# Sampler.net
KiCad netlist of a schematic drawn in Altium Designer
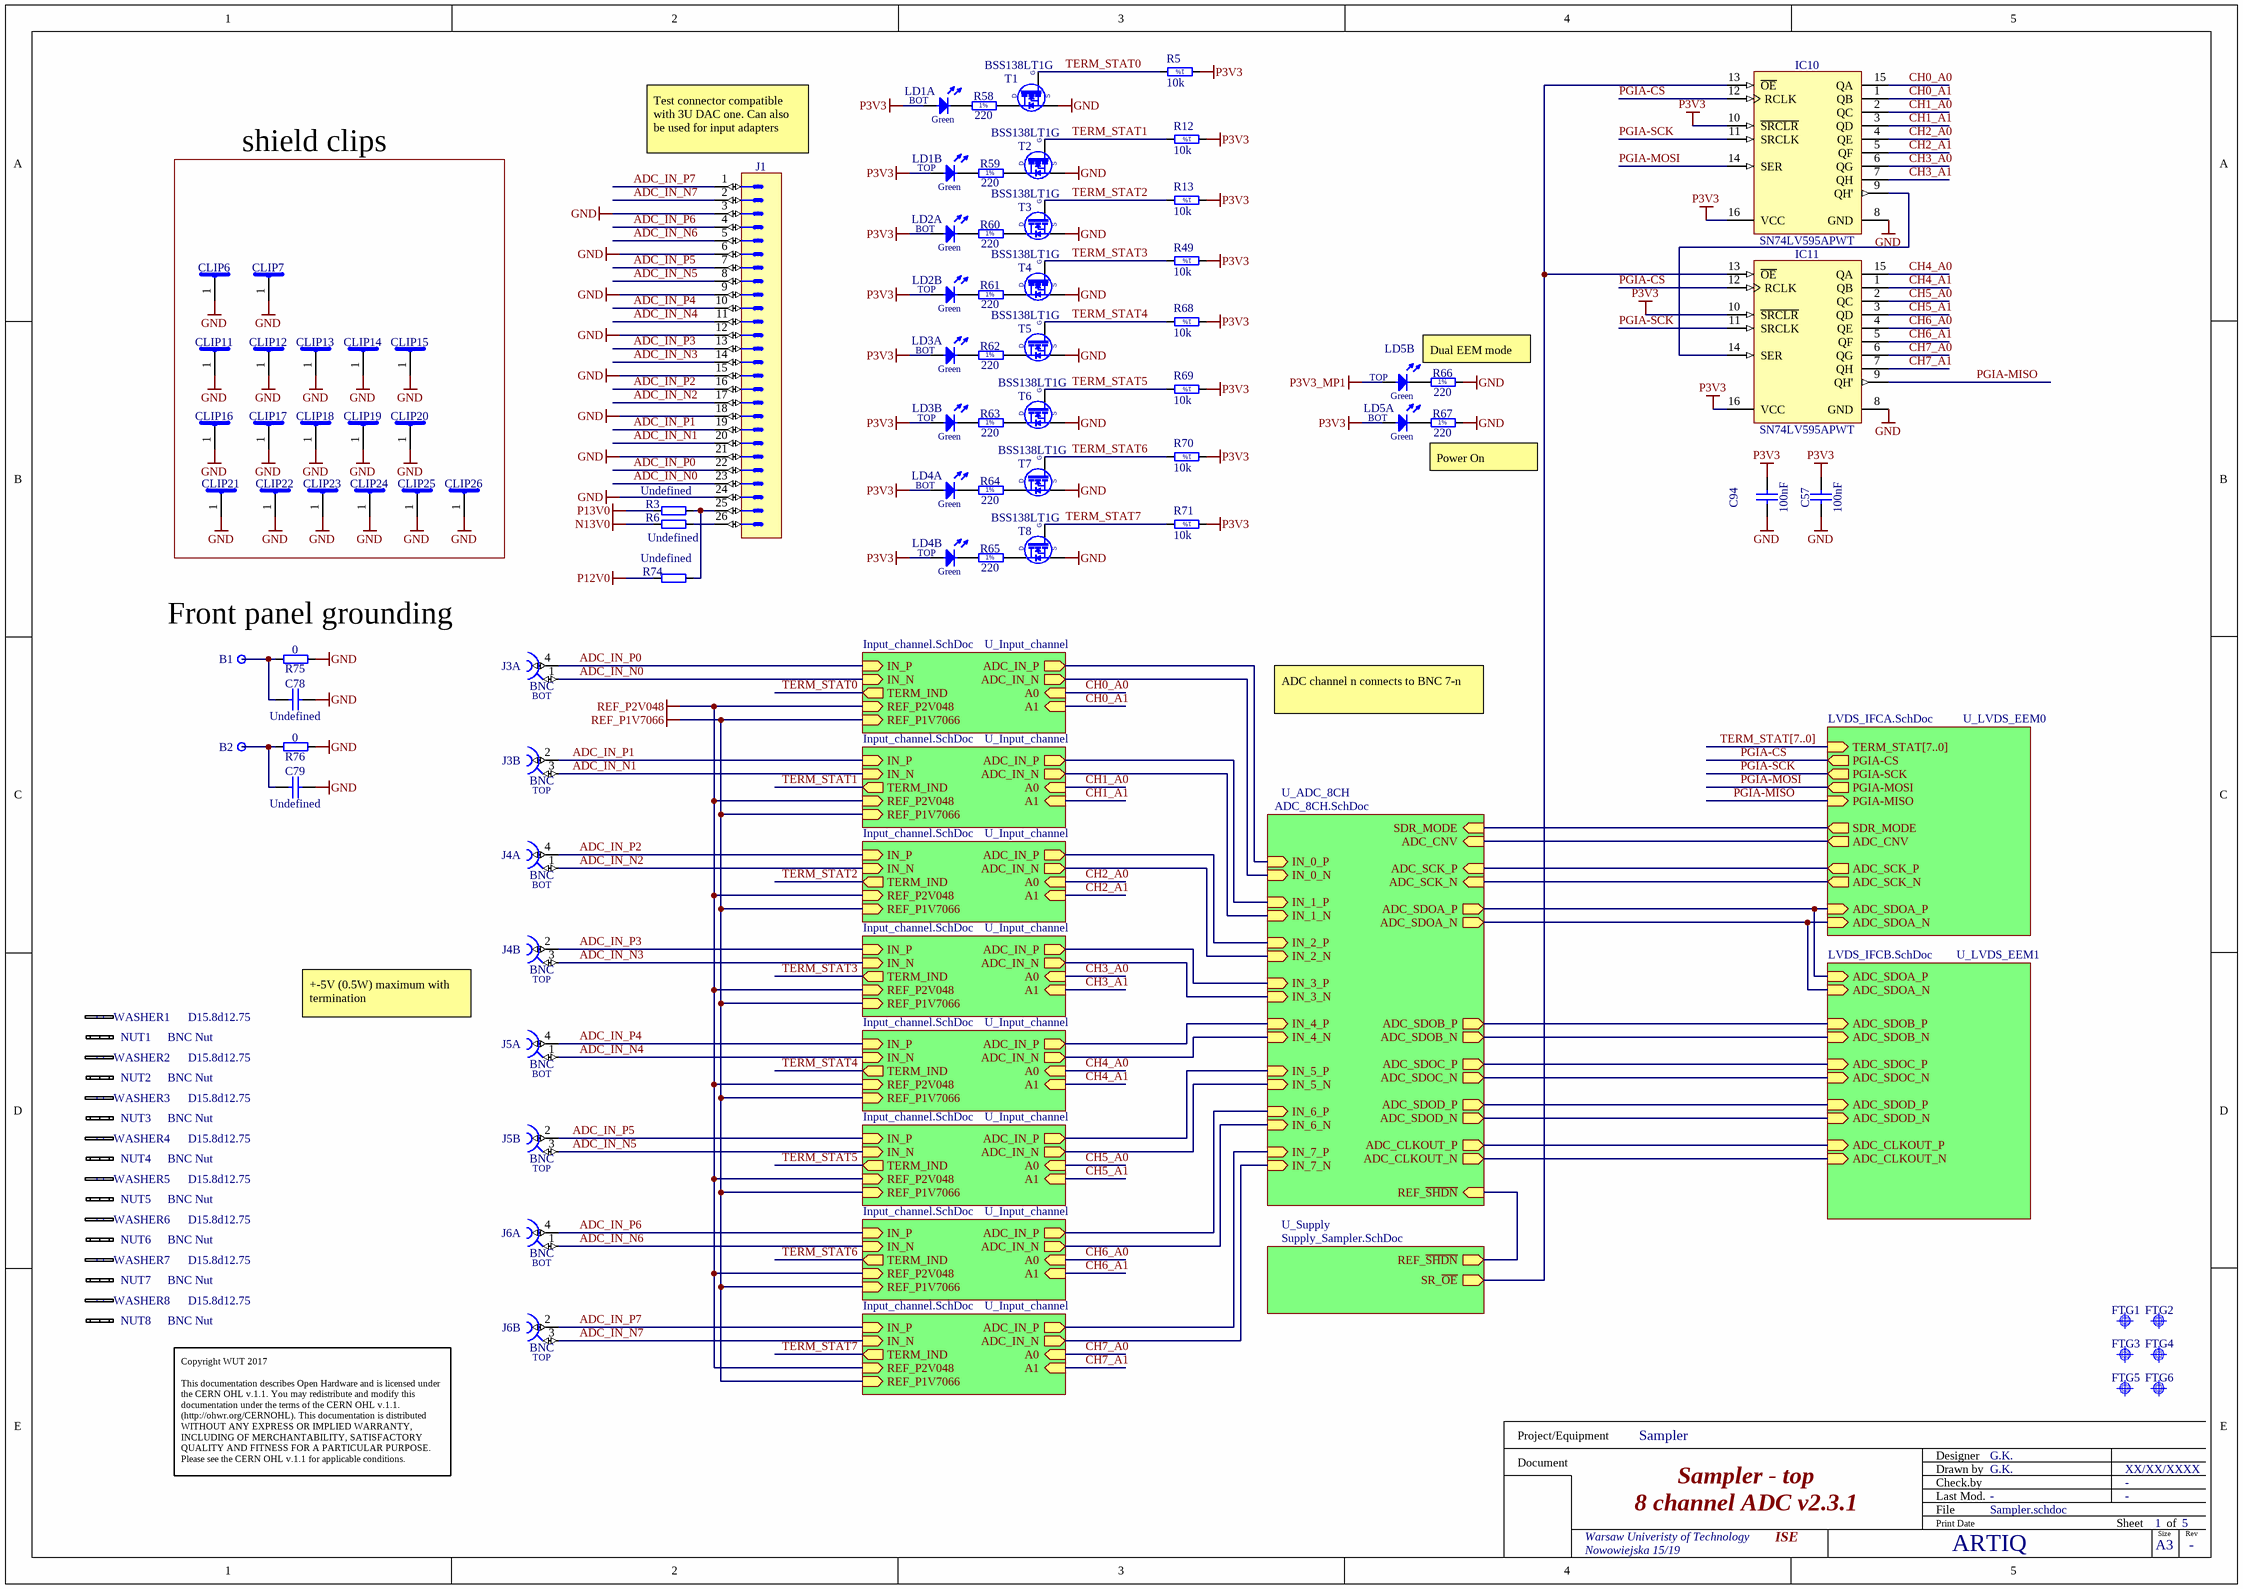
[diagram p0: Sampler.schdoc]

(export (version "E")
  (design (tool "Eeschema 10.0.6"))
  (components
    (comp (ref "B1")
      (value "Plated Hole")
      (footprint "MTG270_500")
      (description "Single Terminal Socket")
      (fields (field (name "PART NUMBER") "PLATED_HOLE2.7_PAD5.0") (field (name "AUTHOR") "CERN DEM JMW"))
      (libsource (lib "Eletro-mechanical") (part "Single Terminal Socket"))
    )
    (comp (ref "B2")
      (value "Plated Hole")
      (footprint "MTG270_500")
      (description "Single Terminal Socket")
      (fields (field (name "PART NUMBER") "PLATED_HOLE2.7_PAD5.0") (field (name "AUTHOR") "CERN DEM JMW"))
      (libsource (lib "Eletro-mechanical") (part "Single Terminal Socket"))
    )
    (comp (ref "C57")
      (value "100nF")
      (footprint "CAPC1608X87N")
      (description "Non-polarised capacitor")
      (fields
        (field (name "PART NUMBER") "CC0603_100NF_50V_10%_X7R")
        (field (name "VOLTAGE") "50V")
        (field (name "AUTHOR") "CERN DEM JLC")
      )
      (libsource (lib "Capacitors") (part "Capacitor - non polarized"))
    )
    (comp (ref "C78")
      (value "Undefined")
      (footprint "CAPC2012X135N")
      (description "Non-polarised capacitor")
      (fields (field (name "PART NUMBER") "CC0805_NO-VALUE") (field (name "AUTHOR") "CERN DEM JLC"))
      (libsource (lib "Capacitors") (part "Capacitor - non polarized"))
    )
    (comp (ref "C79")
      (value "Undefined")
      (footprint "CAPC2012X135N")
      (description "Non-polarised capacitor")
      (fields (field (name "PART NUMBER") "CC0805_NO-VALUE") (field (name "AUTHOR") "CERN DEM JLC"))
      (libsource (lib "Capacitors") (part "Capacitor - non polarized"))
    )
    (comp (ref "C94")
      (value "100nF")
      (footprint "CAPC1608X87N")
      (description "Non-polarised capacitor")
      (fields
        (field (name "PART NUMBER") "CC0603_100NF_50V_10%_X7R")
        (field (name "VOLTAGE") "50V")
        (field (name "AUTHOR") "CERN DEM JLC")
      )
      (libsource (lib "Capacitors") (part "Capacitor - non polarized"))
    )
    (comp (ref "CLIP6")
      (value "S1411-46R")
      (footprint "CLIP_HOLLAND-SHIELDING_LC")
      (description "Surface Mount Clip for PCB Screening Covers")
      (fields (field (name "MANUFACTURER") "HARWIN") (field (name "AUTHOR") "CERN DEM JLC"))
      (libsource (lib "LIBRARY_SCH") (part "SHIELD_CLIP"))
    )
    (comp (ref "CLIP7")
      (value "S1411-46R")
      (footprint "CLIP_HOLLAND-SHIELDING_LC")
      (description "Surface Mount Clip for PCB Screening Covers")
      (fields (field (name "MANUFACTURER") "HARWIN") (field (name "AUTHOR") "CERN DEM JLC"))
      (libsource (lib "LIBRARY_SCH") (part "SHIELD_CLIP"))
    )
    (comp (ref "CLIP11")
      (value "S1411-46R")
      (footprint "CLIP_HOLLAND-SHIELDING_LC")
      (description "Surface Mount Clip for PCB Screening Covers")
      (fields (field (name "MANUFACTURER") "HARWIN") (field (name "AUTHOR") "CERN DEM JLC"))
      (libsource (lib "LIBRARY_SCH") (part "SHIELD_CLIP"))
    )
    (comp (ref "CLIP12")
      (value "S1411-46R")
      (footprint "CLIP_HOLLAND-SHIELDING_LC")
      (description "Surface Mount Clip for PCB Screening Covers")
      (fields (field (name "MANUFACTURER") "HARWIN") (field (name "AUTHOR") "CERN DEM JLC"))
      (libsource (lib "LIBRARY_SCH") (part "SHIELD_CLIP"))
    )
    (comp (ref "CLIP13")
      (value "S1411-46R")
      (footprint "CLIP_HOLLAND-SHIELDING_LC")
      (description "Surface Mount Clip for PCB Screening Covers")
      (fields (field (name "MANUFACTURER") "HARWIN") (field (name "AUTHOR") "CERN DEM JLC"))
      (libsource (lib "LIBRARY_SCH") (part "SHIELD_CLIP"))
    )
    (comp (ref "CLIP14")
      (value "S1411-46R")
      (footprint "CLIP_HOLLAND-SHIELDING_LC")
      (description "Surface Mount Clip for PCB Screening Covers")
      (fields (field (name "MANUFACTURER") "HARWIN") (field (name "AUTHOR") "CERN DEM JLC"))
      (libsource (lib "LIBRARY_SCH") (part "SHIELD_CLIP"))
    )
    (comp (ref "CLIP15")
      (value "S1411-46R")
      (footprint "CLIP_HOLLAND-SHIELDING_LC")
      (description "Surface Mount Clip for PCB Screening Covers")
      (fields (field (name "MANUFACTURER") "HARWIN") (field (name "AUTHOR") "CERN DEM JLC"))
      (libsource (lib "LIBRARY_SCH") (part "SHIELD_CLIP"))
    )
    (comp (ref "CLIP16")
      (value "S1411-46R")
      (footprint "CLIP_HOLLAND-SHIELDING_LC")
      (description "Surface Mount Clip for PCB Screening Covers")
      (fields (field (name "MANUFACTURER") "HARWIN") (field (name "AUTHOR") "CERN DEM JLC"))
      (libsource (lib "LIBRARY_SCH") (part "SHIELD_CLIP"))
    )
    (comp (ref "CLIP17")
      (value "S1411-46R")
      (footprint "CLIP_HOLLAND-SHIELDING_LC")
      (description "Surface Mount Clip for PCB Screening Covers")
      (fields (field (name "MANUFACTURER") "HARWIN") (field (name "AUTHOR") "CERN DEM JLC"))
      (libsource (lib "LIBRARY_SCH") (part "SHIELD_CLIP"))
    )
    (comp (ref "CLIP18")
      (value "S1411-46R")
      (footprint "CLIP_HOLLAND-SHIELDING_LC")
      (description "Surface Mount Clip for PCB Screening Covers")
      (fields (field (name "MANUFACTURER") "HARWIN") (field (name "AUTHOR") "CERN DEM JLC"))
      (libsource (lib "LIBRARY_SCH") (part "SHIELD_CLIP"))
    )
    (comp (ref "CLIP19")
      (value "S1411-46R")
      (footprint "CLIP_HOLLAND-SHIELDING_LC")
      (description "Surface Mount Clip for PCB Screening Covers")
      (fields (field (name "MANUFACTURER") "HARWIN") (field (name "AUTHOR") "CERN DEM JLC"))
      (libsource (lib "LIBRARY_SCH") (part "SHIELD_CLIP"))
    )
    (comp (ref "CLIP20")
      (value "S1411-46R")
      (footprint "CLIP_HOLLAND-SHIELDING_LC")
      (description "Surface Mount Clip for PCB Screening Covers")
      (fields (field (name "MANUFACTURER") "HARWIN") (field (name "AUTHOR") "CERN DEM JLC"))
      (libsource (lib "LIBRARY_SCH") (part "SHIELD_CLIP"))
    )
    (comp (ref "CLIP21")
      (value "S1411-46R")
      (footprint "CLIP_HOLLAND-SHIELDING_LC")
      (description "Surface Mount Clip for PCB Screening Covers")
      (fields (field (name "MANUFACTURER") "HARWIN") (field (name "AUTHOR") "CERN DEM JLC"))
      (libsource (lib "LIBRARY_SCH") (part "SHIELD_CLIP"))
    )
    (comp (ref "CLIP22")
      (value "S1411-46R")
      (footprint "CLIP_HOLLAND-SHIELDING_LC")
      (description "Surface Mount Clip for PCB Screening Covers")
      (fields (field (name "MANUFACTURER") "HARWIN") (field (name "AUTHOR") "CERN DEM JLC"))
      (libsource (lib "LIBRARY_SCH") (part "SHIELD_CLIP"))
    )
    (comp (ref "CLIP23")
      (value "S1411-46R")
      (footprint "CLIP_HOLLAND-SHIELDING_LC")
      (description "Surface Mount Clip for PCB Screening Covers")
      (fields (field (name "MANUFACTURER") "HARWIN") (field (name "AUTHOR") "CERN DEM JLC"))
      (libsource (lib "LIBRARY_SCH") (part "SHIELD_CLIP"))
    )
    (comp (ref "CLIP24")
      (value "S1411-46R")
      (footprint "CLIP_HOLLAND-SHIELDING_LC")
      (description "Surface Mount Clip for PCB Screening Covers")
      (fields (field (name "MANUFACTURER") "HARWIN") (field (name "AUTHOR") "CERN DEM JLC"))
      (libsource (lib "LIBRARY_SCH") (part "SHIELD_CLIP"))
    )
    (comp (ref "CLIP25")
      (value "S1411-46R")
      (footprint "CLIP_HOLLAND-SHIELDING_LC")
      (description "Surface Mount Clip for PCB Screening Covers")
      (fields (field (name "MANUFACTURER") "HARWIN") (field (name "AUTHOR") "CERN DEM JLC"))
      (libsource (lib "LIBRARY_SCH") (part "SHIELD_CLIP"))
    )
    (comp (ref "CLIP26")
      (value "S1411-46R")
      (footprint "CLIP_HOLLAND-SHIELDING_LC")
      (description "Surface Mount Clip for PCB Screening Covers")
      (fields (field (name "MANUFACTURER") "HARWIN") (field (name "AUTHOR") "CERN DEM JLC"))
      (libsource (lib "LIBRARY_SCH") (part "SHIELD_CLIP"))
    )
    (comp (ref "FTG1")
      (value "Use only in PCB")
      (footprint "FIDUCIAL_TOP_C100-200")
      (description "Fiducial Target")
      (fields (field (name "PART NUMBER") "FIDUCIAL_TARGET_C100-200") (field (name "AUTHOR") "CERN DEM JLC"))
      (libsource (lib "Eletro-mechanical") (part "Fiducial Target"))
    )
    (comp (ref "FTG2")
      (value "Use only in PCB")
      (footprint "FIDUCIAL_TOP_C100-200")
      (description "Fiducial Target")
      (fields (field (name "PART NUMBER") "FIDUCIAL_TARGET_C100-200") (field (name "AUTHOR") "CERN DEM JLC"))
      (libsource (lib "Eletro-mechanical") (part "Fiducial Target"))
    )
    (comp (ref "FTG3")
      (value "Use only in PCB")
      (footprint "FIDUCIAL_TOP_S100-200")
      (description "Fiducial Target")
      (fields (field (name "PART NUMBER") "FIDUCIAL_TARGET_S100-200") (field (name "AUTHOR") "CERN DEM JLC"))
      (libsource (lib "Eletro-mechanical") (part "Fiducial Target"))
    )
    (comp (ref "FTG4")
      (value "Use only in PCB")
      (footprint "FIDUCIAL_TOP_S100-200")
      (description "Fiducial Target")
      (fields (field (name "PART NUMBER") "FIDUCIAL_TARGET_S100-200") (field (name "AUTHOR") "CERN DEM JLC"))
      (libsource (lib "Eletro-mechanical") (part "Fiducial Target"))
    )
    (comp (ref "FTG5")
      (value "Use only in PCB")
      (footprint "FIDUCIAL_TOP_S100-200")
      (description "Fiducial Target")
      (fields (field (name "PART NUMBER") "FIDUCIAL_TARGET_S100-200") (field (name "AUTHOR") "CERN DEM JLC"))
      (libsource (lib "Eletro-mechanical") (part "Fiducial Target"))
    )
    (comp (ref "FTG6")
      (value "Use only in PCB")
      (footprint "FIDUCIAL_TOP_S100-200")
      (description "Fiducial Target")
      (fields (field (name "PART NUMBER") "FIDUCIAL_TARGET_S100-200") (field (name "AUTHOR") "CERN DEM JLC"))
      (libsource (lib "Eletro-mechanical") (part "Fiducial Target"))
    )
    (comp (ref "IC10")
      (value "SN74LV595APWT")
      (footprint "SOP65P640X120-16N")
      (description "8-Bit Shift Register With 3-State Output Register")
      (fields (field (name "MANUFACTURER") "TEXAS INSTRUMENTS") (field (name "AUTHOR") "CERN DEM JLC"))
      (libsource (lib "ICs And Semiconductors") (part "74595"))
    )
    (comp (ref "IC11")
      (value "SN74LV595APWT")
      (footprint "SOP65P640X120-16N")
      (description "8-Bit Shift Register With 3-State Output Register")
      (fields (field (name "MANUFACTURER") "TEXAS INSTRUMENTS") (field (name "AUTHOR") "CERN DEM JLC"))
      (libsource (lib "ICs And Semiconductors") (part "74595"))
    )
    (comp (ref "J1")
      (value "Header 26")
      (footprint "3M_N2526-6002RB")
      (description "Connector 26 Male")
      (fields
        (field (name "PART NUMBER") "3M_N2526-6002RB")
        (field (name "MANUFACTURER") "3M")
        (field (name "AUTHOR") "CERN DEM JLC")
      )
      (libsource (lib "Connectors") (part "Connector 26 Male"))
    )
    (comp (ref "J3")
      (value "BNC")
      (footprint "RENHOTEC_RHT-610-0049")
      (description "Dual Right Angle 50 Ohm BNC Jack, White Valox Case")
      (fields
        (field (name "PART NUMBER") "RENHOTEC_RHT-610-0049")
        (field (name "MANUFACTURER") "RENHOTEC")
        (field (name "AUTHOR") "GK")
      )
      (libsource (lib "LIBRARY_SCH") (part "CON_BNC_DUAL"))
    )
    (comp (ref "J4")
      (value "BNC")
      (footprint "RENHOTEC_RHT-610-0049")
      (description "Dual Right Angle 50 Ohm BNC Jack, White Valox Case")
      (fields
        (field (name "PART NUMBER") "RENHOTEC_RHT-610-0049")
        (field (name "MANUFACTURER") "RENHOTEC")
        (field (name "AUTHOR") "GK")
      )
      (libsource (lib "LIBRARY_SCH") (part "CON_BNC_DUAL"))
    )
    (comp (ref "J5")
      (value "BNC")
      (footprint "RENHOTEC_RHT-610-0049")
      (description "Dual Right Angle 50 Ohm BNC Jack, White Valox Case")
      (fields
        (field (name "PART NUMBER") "RENHOTEC_RHT-610-0049")
        (field (name "MANUFACTURER") "RENHOTEC")
        (field (name "AUTHOR") "GK")
      )
      (libsource (lib "LIBRARY_SCH") (part "CON_BNC_DUAL"))
    )
    (comp (ref "J6")
      (value "BNC")
      (footprint "RENHOTEC_RHT-610-0049")
      (description "Dual Right Angle 50 Ohm BNC Jack, White Valox Case")
      (fields
        (field (name "PART NUMBER") "RENHOTEC_RHT-610-0049")
        (field (name "MANUFACTURER") "RENHOTEC")
        (field (name "AUTHOR") "GK")
      )
      (libsource (lib "LIBRARY_SCH") (part "CON_BNC_DUAL"))
    )
    (comp (ref "LD1")
      (value "Green/Green")
      (footprint "LED_DIALIGHT_571-0122F")
      (description "LED x2 Green 1C2A-BOT_3C4A-TOP")
      (fields
        (field (name "PART NUMBER") "LED_DIALIGHT_571-0122F")
        (field (name "MANUFACTURER") "DIALIGHT")
        (field (name "AUTHOR") "CERN DEM JLC")
      )
      (libsource (lib "ICs And Semiconductors") (part "LED x2 Green 1C2A-BOT_3C4A-TOP"))
    )
    (comp (ref "LD2")
      (value "Green/Green")
      (footprint "LED_DIALIGHT_571-0122F")
      (description "LED x2 Green 1C2A-BOT_3C4A-TOP")
      (fields
        (field (name "PART NUMBER") "LED_DIALIGHT_571-0122F")
        (field (name "MANUFACTURER") "DIALIGHT")
        (field (name "AUTHOR") "CERN DEM JLC")
      )
      (libsource (lib "ICs And Semiconductors") (part "LED x2 Green 1C2A-BOT_3C4A-TOP"))
    )
    (comp (ref "LD3")
      (value "Green/Green")
      (footprint "LED_DIALIGHT_571-0122F")
      (description "LED x2 Green 1C2A-BOT_3C4A-TOP")
      (fields
        (field (name "PART NUMBER") "LED_DIALIGHT_571-0122F")
        (field (name "MANUFACTURER") "DIALIGHT")
        (field (name "AUTHOR") "CERN DEM JLC")
      )
      (libsource (lib "ICs And Semiconductors") (part "LED x2 Green 1C2A-BOT_3C4A-TOP"))
    )
    (comp (ref "LD4")
      (value "Green/Green")
      (footprint "LED_DIALIGHT_571-0122F")
      (description "LED x2 Green 1C2A-BOT_3C4A-TOP")
      (fields
        (field (name "PART NUMBER") "LED_DIALIGHT_571-0122F")
        (field (name "MANUFACTURER") "DIALIGHT")
        (field (name "AUTHOR") "CERN DEM JLC")
      )
      (libsource (lib "ICs And Semiconductors") (part "LED x2 Green 1C2A-BOT_3C4A-TOP"))
    )
    (comp (ref "LD5")
      (value "Green/Green")
      (footprint "LED_DIALIGHT_571-0122F")
      (description "LED x2 Green 1C2A-BOT_3C4A-TOP")
      (fields
        (field (name "PART NUMBER") "LED_DIALIGHT_571-0122F")
        (field (name "MANUFACTURER") "DIALIGHT")
        (field (name "AUTHOR") "CERN DEM JLC")
      )
      (libsource (lib "ICs And Semiconductors") (part "LED x2 Green 1C2A-BOT_3C4A-TOP"))
    )
    (comp (ref "NUT1")
      (value "BNC Nut")
      (footprint "TE_1-329631-2")
      (description "BNC nut")
      (fields
        (field (name "PART NUMBER") "TE_1-329631-2")
        (field (name "MANUFACTURER") "TE")
        (field (name "AUTHOR") "CERN DEM JLC")
      )
      (libsource (lib "Mechanical") (part "MECH_BNC_NUT"))
    )
    (comp (ref "NUT2")
      (value "BNC Nut")
      (footprint "TE_1-329631-2")
      (description "BNC nut")
      (fields
        (field (name "PART NUMBER") "TE_1-329631-2")
        (field (name "MANUFACTURER") "TE")
        (field (name "AUTHOR") "CERN DEM JLC")
      )
      (libsource (lib "Mechanical") (part "MECH_BNC_NUT"))
    )
    (comp (ref "NUT3")
      (value "BNC Nut")
      (footprint "TE_1-329631-2")
      (description "BNC nut")
      (fields
        (field (name "PART NUMBER") "TE_1-329631-2")
        (field (name "MANUFACTURER") "TE")
        (field (name "AUTHOR") "CERN DEM JLC")
      )
      (libsource (lib "Mechanical") (part "MECH_BNC_NUT"))
    )
    (comp (ref "NUT4")
      (value "BNC Nut")
      (footprint "TE_1-329631-2")
      (description "BNC nut")
      (fields
        (field (name "PART NUMBER") "TE_1-329631-2")
        (field (name "MANUFACTURER") "TE")
        (field (name "AUTHOR") "CERN DEM JLC")
      )
      (libsource (lib "Mechanical") (part "MECH_BNC_NUT"))
    )
    (comp (ref "NUT5")
      (value "BNC Nut")
      (footprint "TE_1-329631-2")
      (description "BNC nut")
      (fields
        (field (name "PART NUMBER") "TE_1-329631-2")
        (field (name "MANUFACTURER") "TE")
        (field (name "AUTHOR") "CERN DEM JLC")
      )
      (libsource (lib "Mechanical") (part "MECH_BNC_NUT"))
    )
    (comp (ref "NUT6")
      (value "BNC Nut")
      (footprint "TE_1-329631-2")
      (description "BNC nut")
      (fields
        (field (name "PART NUMBER") "TE_1-329631-2")
        (field (name "MANUFACTURER") "TE")
        (field (name "AUTHOR") "CERN DEM JLC")
      )
      (libsource (lib "Mechanical") (part "MECH_BNC_NUT"))
    )
    (comp (ref "NUT7")
      (value "BNC Nut")
      (footprint "TE_1-329631-2")
      (description "BNC nut")
      (fields
        (field (name "PART NUMBER") "TE_1-329631-2")
        (field (name "MANUFACTURER") "TE")
        (field (name "AUTHOR") "CERN DEM JLC")
      )
      (libsource (lib "Mechanical") (part "MECH_BNC_NUT"))
    )
    (comp (ref "NUT8")
      (value "BNC Nut")
      (footprint "TE_1-329631-2")
      (description "BNC nut")
      (fields
        (field (name "PART NUMBER") "TE_1-329631-2")
        (field (name "MANUFACTURER") "TE")
        (field (name "AUTHOR") "CERN DEM JLC")
      )
      (libsource (lib "Mechanical") (part "MECH_BNC_NUT"))
    )
    (comp (ref "R3")
      (value "Undefined")
      (footprint "RESC1608X55N")
      (description "Resistor")
      (fields (field (name "PART NUMBER") "R0603_NO-VALUE") (field (name "AUTHOR") "CERN DEM JLC"))
      (libsource (lib "Resistors") (part "Resistor"))
    )
    (comp (ref "R5")
      (value "10k")
      (footprint "RESC1005X40N")
      (description "Resistor - 1%")
      (fields
        (field (name "PART NUMBER") "R0402_10K_1%_0.0625W_100PPM")
        (field (name "POWER") "0.0625W")
        (field (name "AUTHOR") "CERN DEM JLC")
      )
      (libsource (lib "Resistors") (part "Resistor - 1%"))
    )
    (comp (ref "R6")
      (value "Undefined")
      (footprint "RESC1608X55N")
      (description "Resistor")
      (fields (field (name "PART NUMBER") "R0603_NO-VALUE") (field (name "AUTHOR") "CERN DEM JLC"))
      (libsource (lib "Resistors") (part "Resistor"))
    )
    (comp (ref "R12")
      (value "10k")
      (footprint "RESC1005X40N")
      (description "Resistor - 1%")
      (fields
        (field (name "PART NUMBER") "R0402_10K_1%_0.0625W_100PPM")
        (field (name "POWER") "0.0625W")
        (field (name "AUTHOR") "CERN DEM JLC")
      )
      (libsource (lib "Resistors") (part "Resistor - 1%"))
    )
    (comp (ref "R13")
      (value "10k")
      (footprint "RESC1005X40N")
      (description "Resistor - 1%")
      (fields
        (field (name "PART NUMBER") "R0402_10K_1%_0.0625W_100PPM")
        (field (name "POWER") "0.0625W")
        (field (name "AUTHOR") "CERN DEM JLC")
      )
      (libsource (lib "Resistors") (part "Resistor - 1%"))
    )
    (comp (ref "R49")
      (value "10k")
      (footprint "RESC1005X40N")
      (description "Resistor - 1%")
      (fields
        (field (name "PART NUMBER") "R0402_10K_1%_0.0625W_100PPM")
        (field (name "POWER") "0.0625W")
        (field (name "AUTHOR") "CERN DEM JLC")
      )
      (libsource (lib "Resistors") (part "Resistor - 1%"))
    )
    (comp (ref "R58")
      (value "220")
      (footprint "RESC1608X55N")
      (description "Resistor - 1%")
      (fields
        (field (name "PART NUMBER") "R0603_220R_1%_0.1W_100PPM")
        (field (name "POWER") "0.1W")
        (field (name "AUTHOR") "CERN DEM JLC")
      )
      (libsource (lib "Resistors") (part "Resistor - 1%"))
    )
    (comp (ref "R59")
      (value "220")
      (footprint "RESC1608X55N")
      (description "Resistor - 1%")
      (fields
        (field (name "PART NUMBER") "R0603_220R_1%_0.1W_100PPM")
        (field (name "POWER") "0.1W")
        (field (name "AUTHOR") "CERN DEM JLC")
      )
      (libsource (lib "Resistors") (part "Resistor - 1%"))
    )
    (comp (ref "R60")
      (value "220")
      (footprint "RESC1608X55N")
      (description "Resistor - 1%")
      (fields
        (field (name "PART NUMBER") "R0603_220R_1%_0.1W_100PPM")
        (field (name "POWER") "0.1W")
        (field (name "AUTHOR") "CERN DEM JLC")
      )
      (libsource (lib "Resistors") (part "Resistor - 1%"))
    )
    (comp (ref "R61")
      (value "220")
      (footprint "RESC1608X55N")
      (description "Resistor - 1%")
      (fields
        (field (name "PART NUMBER") "R0603_220R_1%_0.1W_100PPM")
        (field (name "POWER") "0.1W")
        (field (name "AUTHOR") "CERN DEM JLC")
      )
      (libsource (lib "Resistors") (part "Resistor - 1%"))
    )
    (comp (ref "R62")
      (value "220")
      (footprint "RESC1608X55N")
      (description "Resistor - 1%")
      (fields
        (field (name "PART NUMBER") "R0603_220R_1%_0.1W_100PPM")
        (field (name "POWER") "0.1W")
        (field (name "AUTHOR") "CERN DEM JLC")
      )
      (libsource (lib "Resistors") (part "Resistor - 1%"))
    )
    (comp (ref "R63")
      (value "220")
      (footprint "RESC1608X55N")
      (description "Resistor - 1%")
      (fields
        (field (name "PART NUMBER") "R0603_220R_1%_0.1W_100PPM")
        (field (name "POWER") "0.1W")
        (field (name "AUTHOR") "CERN DEM JLC")
      )
      (libsource (lib "Resistors") (part "Resistor - 1%"))
    )
    (comp (ref "R64")
      (value "220")
      (footprint "RESC1608X55N")
      (description "Resistor - 1%")
      (fields
        (field (name "PART NUMBER") "R0603_220R_1%_0.1W_100PPM")
        (field (name "POWER") "0.1W")
        (field (name "AUTHOR") "CERN DEM JLC")
      )
      (libsource (lib "Resistors") (part "Resistor - 1%"))
    )
    (comp (ref "R65")
      (value "220")
      (footprint "RESC1608X55N")
      (description "Resistor - 1%")
      (fields
        (field (name "PART NUMBER") "R0603_220R_1%_0.1W_100PPM")
        (field (name "POWER") "0.1W")
        (field (name "AUTHOR") "CERN DEM JLC")
      )
      (libsource (lib "Resistors") (part "Resistor - 1%"))
    )
    (comp (ref "R66")
      (value "220")
      (footprint "RESC1608X55N")
      (description "Resistor - 1%")
      (fields
        (field (name "PART NUMBER") "R0603_220R_1%_0.1W_100PPM")
        (field (name "POWER") "0.1W")
        (field (name "AUTHOR") "CERN DEM JLC")
      )
      (libsource (lib "Resistors") (part "Resistor - 1%"))
    )
    (comp (ref "R67")
      (value "220")
      (footprint "RESC1608X55N")
      (description "Resistor - 1%")
      (fields
        (field (name "PART NUMBER") "R0603_220R_1%_0.1W_100PPM")
        (field (name "POWER") "0.1W")
        (field (name "AUTHOR") "CERN DEM JLC")
      )
      (libsource (lib "Resistors") (part "Resistor - 1%"))
    )
    (comp (ref "R68")
      (value "10k")
      (footprint "RESC1005X40N")
      (description "Resistor - 1%")
      (fields
        (field (name "PART NUMBER") "R0402_10K_1%_0.0625W_100PPM")
        (field (name "POWER") "0.0625W")
        (field (name "AUTHOR") "CERN DEM JLC")
      )
      (libsource (lib "Resistors") (part "Resistor - 1%"))
    )
    (comp (ref "R69")
      (value "10k")
      (footprint "RESC1005X40N")
      (description "Resistor - 1%")
      (fields
        (field (name "PART NUMBER") "R0402_10K_1%_0.0625W_100PPM")
        (field (name "POWER") "0.0625W")
        (field (name "AUTHOR") "CERN DEM JLC")
      )
      (libsource (lib "Resistors") (part "Resistor - 1%"))
    )
    (comp (ref "R70")
      (value "10k")
      (footprint "RESC1005X40N")
      (description "Resistor - 1%")
      (fields
        (field (name "PART NUMBER") "R0402_10K_1%_0.0625W_100PPM")
        (field (name "POWER") "0.0625W")
        (field (name "AUTHOR") "CERN DEM JLC")
      )
      (libsource (lib "Resistors") (part "Resistor - 1%"))
    )
    (comp (ref "R71")
      (value "10k")
      (footprint "RESC1005X40N")
      (description "Resistor - 1%")
      (fields
        (field (name "PART NUMBER") "R0402_10K_1%_0.0625W_100PPM")
        (field (name "POWER") "0.0625W")
        (field (name "AUTHOR") "CERN DEM JLC")
      )
      (libsource (lib "Resistors") (part "Resistor - 1%"))
    )
    (comp (ref "R74")
      (value "Undefined")
      (footprint "RESC1608X55N")
      (description "Resistor")
      (fields (field (name "PART NUMBER") "R0603_NO-VALUE") (field (name "AUTHOR") "CERN DEM JLC"))
      (libsource (lib "Resistors") (part "Resistor"))
    )
    (comp (ref "R75")
      (value "0")
      (footprint "RESC1608X55N")
      (description "Resistor")
      (fields
        (field (name "PART NUMBER") "R0603_0R_JUMPER")
        (field (name "MANUFACTURER") "GENERIC")
        (field (name "AUTHOR") "CERN DEM JLC")
      )
      (libsource (lib "Resistors") (part "Resistor"))
    )
    (comp (ref "R76")
      (value "0")
      (footprint "RESC1608X55N")
      (description "Resistor")
      (fields
        (field (name "PART NUMBER") "R0603_0R_JUMPER")
        (field (name "MANUFACTURER") "GENERIC")
        (field (name "AUTHOR") "CERN DEM JLC")
      )
      (libsource (lib "Resistors") (part "Resistor"))
    )
    (comp (ref "T1")
      (value "BSS138LT1G")
      (footprint "SOT95P240X110-3N")
      (description "N-CHANNEL MOSFET WITH DIODE")
      (fields (field (name "MANUFACTURER") "ON SEMICONDUCTOR") (field (name "AUTHOR") "CERN DEM JLC"))
      (libsource (lib "ICs And Semiconductors") (part "N-MOSFET-D 1G 2S 3D"))
    )
    (comp (ref "T2")
      (value "BSS138LT1G")
      (footprint "SOT95P240X110-3N")
      (description "N-CHANNEL MOSFET WITH DIODE")
      (fields (field (name "MANUFACTURER") "ON SEMICONDUCTOR") (field (name "AUTHOR") "CERN DEM JLC"))
      (libsource (lib "ICs And Semiconductors") (part "N-MOSFET-D 1G 2S 3D"))
    )
    (comp (ref "T3")
      (value "BSS138LT1G")
      (footprint "SOT95P240X110-3N")
      (description "N-CHANNEL MOSFET WITH DIODE")
      (fields (field (name "MANUFACTURER") "ON SEMICONDUCTOR") (field (name "AUTHOR") "CERN DEM JLC"))
      (libsource (lib "ICs And Semiconductors") (part "N-MOSFET-D 1G 2S 3D"))
    )
    (comp (ref "T4")
      (value "BSS138LT1G")
      (footprint "SOT95P240X110-3N")
      (description "N-CHANNEL MOSFET WITH DIODE")
      (fields (field (name "MANUFACTURER") "ON SEMICONDUCTOR") (field (name "AUTHOR") "CERN DEM JLC"))
      (libsource (lib "ICs And Semiconductors") (part "N-MOSFET-D 1G 2S 3D"))
    )
    (comp (ref "T5")
      (value "BSS138LT1G")
      (footprint "SOT95P240X110-3N")
      (description "N-CHANNEL MOSFET WITH DIODE")
      (fields (field (name "MANUFACTURER") "ON SEMICONDUCTOR") (field (name "AUTHOR") "CERN DEM JLC"))
      (libsource (lib "ICs And Semiconductors") (part "N-MOSFET-D 1G 2S 3D"))
    )
    (comp (ref "T6")
      (value "BSS138LT1G")
      (footprint "SOT95P240X110-3N")
      (description "N-CHANNEL MOSFET WITH DIODE")
      (fields (field (name "MANUFACTURER") "ON SEMICONDUCTOR") (field (name "AUTHOR") "CERN DEM JLC"))
      (libsource (lib "ICs And Semiconductors") (part "N-MOSFET-D 1G 2S 3D"))
    )
    (comp (ref "T7")
      (value "BSS138LT1G")
      (footprint "SOT95P240X110-3N")
      (description "N-CHANNEL MOSFET WITH DIODE")
      (fields (field (name "MANUFACTURER") "ON SEMICONDUCTOR") (field (name "AUTHOR") "CERN DEM JLC"))
      (libsource (lib "ICs And Semiconductors") (part "N-MOSFET-D 1G 2S 3D"))
    )
    (comp (ref "T8")
      (value "BSS138LT1G")
      (footprint "SOT95P240X110-3N")
      (description "N-CHANNEL MOSFET WITH DIODE")
      (fields (field (name "MANUFACTURER") "ON SEMICONDUCTOR") (field (name "AUTHOR") "CERN DEM JLC"))
      (libsource (lib "ICs And Semiconductors") (part "N-MOSFET-D 1G 2S 3D"))
    )
    (comp (ref "WASHER1")
      (value "D15.8d12.75")
      (footprint "TE_1-1634817-0")
      (description "BNC Washer")
      (fields
        (field (name "PART NUMBER") "TE_1-1634817-0")
        (field (name "MANUFACTURER") "TE")
        (field (name "AUTHOR") "GK")
      )
      (libsource (lib "Mechanical") (part "MECH_BNC_WASHER"))
    )
    (comp (ref "WASHER2")
      (value "D15.8d12.75")
      (footprint "TE_1-1634817-0")
      (description "BNC Washer")
      (fields
        (field (name "PART NUMBER") "TE_1-1634817-0")
        (field (name "MANUFACTURER") "TE")
        (field (name "AUTHOR") "GK")
      )
      (libsource (lib "Mechanical") (part "MECH_BNC_WASHER"))
    )
    (comp (ref "WASHER3")
      (value "D15.8d12.75")
      (footprint "TE_1-1634817-0")
      (description "BNC Washer")
      (fields
        (field (name "PART NUMBER") "TE_1-1634817-0")
        (field (name "MANUFACTURER") "TE")
        (field (name "AUTHOR") "GK")
      )
      (libsource (lib "Mechanical") (part "MECH_BNC_WASHER"))
    )
    (comp (ref "WASHER4")
      (value "D15.8d12.75")
      (footprint "TE_1-1634817-0")
      (description "BNC Washer")
      (fields
        (field (name "PART NUMBER") "TE_1-1634817-0")
        (field (name "MANUFACTURER") "TE")
        (field (name "AUTHOR") "GK")
      )
      (libsource (lib "Mechanical") (part "MECH_BNC_WASHER"))
    )
    (comp (ref "WASHER5")
      (value "D15.8d12.75")
      (footprint "TE_1-1634817-0")
      (description "BNC Washer")
      (fields
        (field (name "PART NUMBER") "TE_1-1634817-0")
        (field (name "MANUFACTURER") "TE")
        (field (name "AUTHOR") "GK")
      )
      (libsource (lib "Mechanical") (part "MECH_BNC_WASHER"))
    )
    (comp (ref "WASHER6")
      (value "D15.8d12.75")
      (footprint "TE_1-1634817-0")
      (description "BNC Washer")
      (fields
        (field (name "PART NUMBER") "TE_1-1634817-0")
        (field (name "MANUFACTURER") "TE")
        (field (name "AUTHOR") "GK")
      )
      (libsource (lib "Mechanical") (part "MECH_BNC_WASHER"))
    )
    (comp (ref "WASHER7")
      (value "D15.8d12.75")
      (footprint "TE_1-1634817-0")
      (description "BNC Washer")
      (fields
        (field (name "PART NUMBER") "TE_1-1634817-0")
        (field (name "MANUFACTURER") "TE")
        (field (name "AUTHOR") "GK")
      )
      (libsource (lib "Mechanical") (part "MECH_BNC_WASHER"))
    )
    (comp (ref "WASHER8")
      (value "D15.8d12.75")
      (footprint "TE_1-1634817-0")
      (description "BNC Washer")
      (fields
        (field (name "PART NUMBER") "TE_1-1634817-0")
        (field (name "MANUFACTURER") "TE")
        (field (name "AUTHOR") "GK")
      )
      (libsource (lib "Mechanical") (part "MECH_BNC_WASHER"))
    )
  )
  (nets
    (net (code "5") (name "/ADC_IN_N0") (class "Default")
      (node (ref "J1") (pin "23") (pinfunction "23_23") (pintype "bidirectional"))
      (node (ref "J3") (pin "1") (pinfunction "1_1") (pintype "bidirectional"))
    )
    (net (code "6") (name "/ADC_IN_N1") (class "Default")
      (node (ref "J1") (pin "20") (pinfunction "20_20") (pintype "bidirectional"))
      (node (ref "J3") (pin "3") (pinfunction "3_3") (pintype "bidirectional"))
    )
    (net (code "7") (name "/ADC_IN_N2") (class "Default")
      (node (ref "J1") (pin "17") (pinfunction "17_17") (pintype "bidirectional"))
      (node (ref "J4") (pin "1") (pinfunction "1_1") (pintype "bidirectional"))
    )
    (net (code "8") (name "/ADC_IN_N3") (class "Default")
      (node (ref "J1") (pin "14") (pinfunction "14_14") (pintype "bidirectional"))
      (node (ref "J4") (pin "3") (pinfunction "3_3") (pintype "bidirectional"))
    )
    (net (code "9") (name "/ADC_IN_N4") (class "Default")
      (node (ref "J1") (pin "11") (pinfunction "11_11") (pintype "bidirectional"))
      (node (ref "J5") (pin "1") (pinfunction "1_1") (pintype "bidirectional"))
    )
    (net (code "10") (name "/ADC_IN_N5") (class "Default")
      (node (ref "J1") (pin "8") (pinfunction "8_8") (pintype "bidirectional"))
      (node (ref "J5") (pin "3") (pinfunction "3_3") (pintype "bidirectional"))
    )
    (net (code "11") (name "/ADC_IN_N6") (class "Default")
      (node (ref "J1") (pin "5") (pinfunction "5_5") (pintype "bidirectional"))
      (node (ref "J6") (pin "1") (pinfunction "1_1") (pintype "bidirectional"))
    )
    (net (code "12") (name "/ADC_IN_N7") (class "Default")
      (node (ref "J1") (pin "2") (pinfunction "2_2") (pintype "bidirectional"))
      (node (ref "J6") (pin "3") (pinfunction "3_3") (pintype "bidirectional"))
    )
    (net (code "21") (name "/ADC_IN_P0") (class "Default")
      (node (ref "J1") (pin "22") (pinfunction "22_22") (pintype "bidirectional"))
      (node (ref "J3") (pin "4") (pinfunction "4_4") (pintype "bidirectional"))
    )
    (net (code "22") (name "/ADC_IN_P1") (class "Default")
      (node (ref "J1") (pin "19") (pinfunction "19_19") (pintype "bidirectional"))
      (node (ref "J3") (pin "2") (pinfunction "2_2") (pintype "bidirectional"))
    )
    (net (code "23") (name "/ADC_IN_P2") (class "Default")
      (node (ref "J1") (pin "16") (pinfunction "16_16") (pintype "bidirectional"))
      (node (ref "J4") (pin "4") (pinfunction "4_4") (pintype "bidirectional"))
    )
    (net (code "24") (name "/ADC_IN_P3") (class "Default")
      (node (ref "J1") (pin "13") (pinfunction "13_13") (pintype "bidirectional"))
      (node (ref "J4") (pin "2") (pinfunction "2_2") (pintype "bidirectional"))
    )
    (net (code "25") (name "/ADC_IN_P4") (class "Default")
      (node (ref "J1") (pin "10") (pinfunction "10_10") (pintype "bidirectional"))
      (node (ref "J5") (pin "4") (pinfunction "4_4") (pintype "bidirectional"))
    )
    (net (code "26") (name "/ADC_IN_P5") (class "Default")
      (node (ref "J1") (pin "7") (pinfunction "7_7") (pintype "bidirectional"))
      (node (ref "J5") (pin "2") (pinfunction "2_2") (pintype "bidirectional"))
    )
    (net (code "27") (name "/ADC_IN_P6") (class "Default")
      (node (ref "J1") (pin "4") (pinfunction "4_4") (pintype "bidirectional"))
      (node (ref "J6") (pin "4") (pinfunction "4_4") (pintype "bidirectional"))
    )
    (net (code "28") (name "/ADC_IN_P7") (class "Default")
      (node (ref "J1") (pin "1") (pinfunction "1_1") (pintype "bidirectional"))
      (node (ref "J6") (pin "2") (pinfunction "2_2") (pintype "bidirectional"))
    )
    (net (code "46") (name "/CH0_A0") (class "Default")
      (node (ref "IC10") (pin "15") (pinfunction "QA_15") (pintype "tri_state"))
    )
    (net (code "47") (name "/CH0_A1") (class "Default")
      (node (ref "IC10") (pin "1") (pinfunction "QB_1") (pintype "tri_state"))
    )
    (net (code "48") (name "/CH1_A0") (class "Default")
      (node (ref "IC10") (pin "2") (pinfunction "QC_2") (pintype "tri_state"))
    )
    (net (code "49") (name "/CH1_A1") (class "Default")
      (node (ref "IC10") (pin "3") (pinfunction "QD_3") (pintype "tri_state"))
    )
    (net (code "50") (name "/CH2_A0") (class "Default")
      (node (ref "IC10") (pin "4") (pinfunction "QE_4") (pintype "tri_state"))
    )
    (net (code "51") (name "/CH2_A1") (class "Default")
      (node (ref "IC10") (pin "5") (pinfunction "QF_5") (pintype "tri_state"))
    )
    (net (code "52") (name "/CH3_A0") (class "Default")
      (node (ref "IC10") (pin "6") (pinfunction "QG_6") (pintype "tri_state"))
    )
    (net (code "53") (name "/CH3_A1") (class "Default")
      (node (ref "IC10") (pin "7") (pinfunction "QH_7") (pintype "tri_state"))
    )
    (net (code "54") (name "/CH4_A0") (class "Default")
      (node (ref "IC11") (pin "15") (pinfunction "QA_15") (pintype "tri_state"))
    )
    (net (code "55") (name "/CH4_A1") (class "Default")
      (node (ref "IC11") (pin "1") (pinfunction "QB_1") (pintype "tri_state"))
    )
    (net (code "56") (name "/CH5_A0") (class "Default")
      (node (ref "IC11") (pin "2") (pinfunction "QC_2") (pintype "tri_state"))
    )
    (net (code "57") (name "/CH5_A1") (class "Default")
      (node (ref "IC11") (pin "3") (pinfunction "QD_3") (pintype "tri_state"))
    )
    (net (code "58") (name "/CH6_A0") (class "Default")
      (node (ref "IC11") (pin "4") (pinfunction "QE_4") (pintype "tri_state"))
    )
    (net (code "59") (name "/CH6_A1") (class "Default")
      (node (ref "IC11") (pin "5") (pinfunction "QF_5") (pintype "tri_state"))
    )
    (net (code "60") (name "/CH7_A0") (class "Default")
      (node (ref "IC11") (pin "6") (pinfunction "QG_6") (pintype "tri_state"))
    )
    (net (code "61") (name "/CH7_A1") (class "Default")
      (node (ref "IC11") (pin "7") (pinfunction "QH_7") (pintype "tri_state"))
    )
    (net (code "62") (name "/PGIA-CS") (class "Default")
      (node (ref "IC10") (pin "12") (pinfunction "RCLK_12") (pintype "input"))
      (node (ref "IC11") (pin "12") (pinfunction "RCLK_12") (pintype "input"))
    )
    (net (code "63") (name "/PGIA-MISO") (class "Default")
      (node (ref "IC11") (pin "9") (pinfunction "QH'_9") (pintype "output"))
    )
    (net (code "64") (name "/PGIA-MOSI") (class "Default")
      (node (ref "IC10") (pin "14") (pinfunction "SER_14") (pintype "input"))
    )
    (net (code "65") (name "/PGIA-SCK") (class "Default")
      (node (ref "IC10") (pin "11") (pinfunction "SRCLK_11") (pintype "input"))
      (node (ref "IC11") (pin "11") (pinfunction "SRCLK_11") (pintype "input"))
    )
    (net (code "68") (name "/SR_~{OE}") (class "Default")
      (node (ref "IC10") (pin "13") (pinfunction "~{OE}_13") (pintype "input"))
      (node (ref "IC11") (pin "13") (pinfunction "~{OE}_13") (pintype "input"))
    )
    (net (code "69") (name "/TERM_STAT0") (class "Default")
      (node (ref "R5") (pin "2") (pinfunction "2_2") (pintype "passive"))
      (node (ref "T1") (pin "1") (pinfunction "G_1") (pintype "passive"))
    )
    (net (code "70") (name "/TERM_STAT1") (class "Default")
      (node (ref "R12") (pin "2") (pinfunction "2_2") (pintype "passive"))
      (node (ref "T2") (pin "1") (pinfunction "G_1") (pintype "passive"))
    )
    (net (code "71") (name "/TERM_STAT2") (class "Default")
      (node (ref "R13") (pin "2") (pinfunction "2_2") (pintype "passive"))
      (node (ref "T3") (pin "1") (pinfunction "G_1") (pintype "passive"))
    )
    (net (code "72") (name "/TERM_STAT3") (class "Default")
      (node (ref "R49") (pin "2") (pinfunction "2_2") (pintype "passive"))
      (node (ref "T4") (pin "1") (pinfunction "G_1") (pintype "passive"))
    )
    (net (code "73") (name "/TERM_STAT4") (class "Default")
      (node (ref "R68") (pin "2") (pinfunction "2_2") (pintype "passive"))
      (node (ref "T5") (pin "1") (pinfunction "G_1") (pintype "passive"))
    )
    (net (code "74") (name "/TERM_STAT5") (class "Default")
      (node (ref "R69") (pin "2") (pinfunction "2_2") (pintype "passive"))
      (node (ref "T6") (pin "1") (pinfunction "G_1") (pintype "passive"))
    )
    (net (code "75") (name "/TERM_STAT6") (class "Default")
      (node (ref "R70") (pin "2") (pinfunction "2_2") (pintype "passive"))
      (node (ref "T7") (pin "1") (pinfunction "G_1") (pintype "passive"))
    )
    (net (code "76") (name "/TERM_STAT7") (class "Default")
      (node (ref "R71") (pin "2") (pinfunction "2_2") (pintype "passive"))
      (node (ref "T8") (pin "1") (pinfunction "G_1") (pintype "passive"))
    )
    (net (code "78") (name "GND") (class "Default")
      (node (ref "C57") (pin "1") (pinfunction "1_1") (pintype "passive"))
      (node (ref "C78") (pin "2") (pinfunction "2_2") (pintype "passive"))
      (node (ref "C79") (pin "2") (pinfunction "2_2") (pintype "passive"))
      (node (ref "C94") (pin "1") (pinfunction "1_1") (pintype "passive"))
      (node (ref "CLIP11") (pin "1") (pinfunction "1_1") (pintype "passive"))
      (node (ref "CLIP12") (pin "1") (pinfunction "1_1") (pintype "passive"))
      (node (ref "CLIP13") (pin "1") (pinfunction "1_1") (pintype "passive"))
      (node (ref "CLIP14") (pin "1") (pinfunction "1_1") (pintype "passive"))
      (node (ref "CLIP15") (pin "1") (pinfunction "1_1") (pintype "passive"))
      (node (ref "CLIP16") (pin "1") (pinfunction "1_1") (pintype "passive"))
      (node (ref "CLIP17") (pin "1") (pinfunction "1_1") (pintype "passive"))
      (node (ref "CLIP18") (pin "1") (pinfunction "1_1") (pintype "passive"))
      (node (ref "CLIP19") (pin "1") (pinfunction "1_1") (pintype "passive"))
      (node (ref "CLIP20") (pin "1") (pinfunction "1_1") (pintype "passive"))
      (node (ref "CLIP21") (pin "1") (pinfunction "1_1") (pintype "passive"))
      (node (ref "CLIP22") (pin "1") (pinfunction "1_1") (pintype "passive"))
      (node (ref "CLIP23") (pin "1") (pinfunction "1_1") (pintype "passive"))
      (node (ref "CLIP24") (pin "1") (pinfunction "1_1") (pintype "passive"))
      (node (ref "CLIP25") (pin "1") (pinfunction "1_1") (pintype "passive"))
      (node (ref "CLIP26") (pin "1") (pinfunction "1_1") (pintype "passive"))
      (node (ref "CLIP6") (pin "1") (pinfunction "1_1") (pintype "passive"))
      (node (ref "CLIP7") (pin "1") (pinfunction "1_1") (pintype "passive"))
      (node (ref "IC10") (pin "8") (pinfunction "GND_8") (pintype "power_in"))
      (node (ref "IC11") (pin "8") (pinfunction "GND_8") (pintype "power_in"))
      (node (ref "J1") (pin "12") (pinfunction "12_12") (pintype "bidirectional"))
      (node (ref "J1") (pin "15") (pinfunction "15_15") (pintype "bidirectional"))
      (node (ref "J1") (pin "18") (pinfunction "18_18") (pintype "bidirectional"))
      (node (ref "J1") (pin "21") (pinfunction "21_21") (pintype "bidirectional"))
      (node (ref "J1") (pin "24") (pinfunction "24_24") (pintype "bidirectional"))
      (node (ref "J1") (pin "3") (pinfunction "3_3") (pintype "bidirectional"))
      (node (ref "J1") (pin "6") (pinfunction "6_6") (pintype "bidirectional"))
      (node (ref "J1") (pin "9") (pinfunction "9_9") (pintype "bidirectional"))
      (node (ref "R66") (pin "2") (pinfunction "2_2") (pintype "passive"))
      (node (ref "R67") (pin "2") (pinfunction "2_2") (pintype "passive"))
      (node (ref "R75") (pin "1") (pinfunction "1_1") (pintype "passive"))
      (node (ref "R76") (pin "1") (pinfunction "1_1") (pintype "passive"))
      (node (ref "T1") (pin "2") (pinfunction "S_2") (pintype "passive"))
      (node (ref "T2") (pin "2") (pinfunction "S_2") (pintype "passive"))
      (node (ref "T3") (pin "2") (pinfunction "S_2") (pintype "passive"))
      (node (ref "T4") (pin "2") (pinfunction "S_2") (pintype "passive"))
      (node (ref "T5") (pin "2") (pinfunction "S_2") (pintype "passive"))
      (node (ref "T6") (pin "2") (pinfunction "S_2") (pintype "passive"))
      (node (ref "T7") (pin "2") (pinfunction "S_2") (pintype "passive"))
      (node (ref "T8") (pin "2") (pinfunction "S_2") (pintype "passive"))
    )
    (net (code "79") (name "N13V0") (class "Default")
      (node (ref "R6") (pin "2") (pinfunction "2_2") (pintype "passive"))
    )
    (net (code "80") (name "Net-(B1-Pad1)") (class "Default")
      (node (ref "B1") (pin "1") (pinfunction "1_1") (pintype "bidirectional"))
      (node (ref "C78") (pin "1") (pinfunction "1_1") (pintype "passive"))
      (node (ref "R75") (pin "2") (pinfunction "2_2") (pintype "passive"))
    )
    (net (code "81") (name "Net-(B2-Pad1)") (class "Default")
      (node (ref "B2") (pin "1") (pinfunction "1_1") (pintype "bidirectional"))
      (node (ref "C79") (pin "1") (pinfunction "1_1") (pintype "passive"))
      (node (ref "R76") (pin "2") (pinfunction "2_2") (pintype "passive"))
    )
    (net (code "82") (name "Net-(IC10-QH')") (class "Default")
      (node (ref "IC10") (pin "9") (pinfunction "QH'_9") (pintype "output"))
      (node (ref "IC11") (pin "14") (pinfunction "SER_14") (pintype "input"))
    )
    (net (code "83") (name "Net-(J1-Pad25)") (class "Default")
      (node (ref "J1") (pin "25") (pinfunction "25_25") (pintype "bidirectional"))
      (node (ref "R3") (pin "1") (pinfunction "1_1") (pintype "passive"))
      (node (ref "R74") (pin "1") (pinfunction "1_1") (pintype "passive"))
    )
    (net (code "84") (name "Net-(J1-Pad26)") (class "Default")
      (node (ref "J1") (pin "26") (pinfunction "26_26") (pintype "bidirectional"))
      (node (ref "R6") (pin "1") (pinfunction "1_1") (pintype "passive"))
    )
    (net (code "85") (name "Net-(LD1A-C)") (class "Default")
      (node (ref "LD1") (pin "1") (pinfunction "C_1") (pintype "passive"))
      (node (ref "R58") (pin "1") (pinfunction "1_1") (pintype "passive"))
    )
    (net (code "86") (name "Net-(LD1B-C)") (class "Default")
      (node (ref "LD1") (pin "3") (pinfunction "C_3") (pintype "passive"))
      (node (ref "R59") (pin "1") (pinfunction "1_1") (pintype "passive"))
    )
    (net (code "87") (name "Net-(LD2A-C)") (class "Default")
      (node (ref "LD2") (pin "1") (pinfunction "C_1") (pintype "passive"))
      (node (ref "R60") (pin "1") (pinfunction "1_1") (pintype "passive"))
    )
    (net (code "88") (name "Net-(LD2B-C)") (class "Default")
      (node (ref "LD2") (pin "3") (pinfunction "C_3") (pintype "passive"))
      (node (ref "R61") (pin "1") (pinfunction "1_1") (pintype "passive"))
    )
    (net (code "89") (name "Net-(LD3A-C)") (class "Default")
      (node (ref "LD3") (pin "1") (pinfunction "C_1") (pintype "passive"))
      (node (ref "R62") (pin "1") (pinfunction "1_1") (pintype "passive"))
    )
    (net (code "90") (name "Net-(LD3B-C)") (class "Default")
      (node (ref "LD3") (pin "3") (pinfunction "C_3") (pintype "passive"))
      (node (ref "R63") (pin "1") (pinfunction "1_1") (pintype "passive"))
    )
    (net (code "91") (name "Net-(LD4A-C)") (class "Default")
      (node (ref "LD4") (pin "1") (pinfunction "C_1") (pintype "passive"))
      (node (ref "R64") (pin "1") (pinfunction "1_1") (pintype "passive"))
    )
    (net (code "92") (name "Net-(LD4B-C)") (class "Default")
      (node (ref "LD4") (pin "3") (pinfunction "C_3") (pintype "passive"))
      (node (ref "R65") (pin "1") (pinfunction "1_1") (pintype "passive"))
    )
    (net (code "93") (name "Net-(LD5A-C)") (class "Default")
      (node (ref "LD5") (pin "1") (pinfunction "C_1") (pintype "passive"))
      (node (ref "R67") (pin "1") (pinfunction "1_1") (pintype "passive"))
    )
    (net (code "94") (name "Net-(LD5B-C)") (class "Default")
      (node (ref "LD5") (pin "3") (pinfunction "C_3") (pintype "passive"))
      (node (ref "R66") (pin "1") (pinfunction "1_1") (pintype "passive"))
    )
    (net (code "95") (name "Net-(T1-D)") (class "Default")
      (node (ref "R58") (pin "2") (pinfunction "2_2") (pintype "passive"))
      (node (ref "T1") (pin "3") (pinfunction "D_3") (pintype "passive"))
    )
    (net (code "96") (name "Net-(T2-D)") (class "Default")
      (node (ref "R59") (pin "2") (pinfunction "2_2") (pintype "passive"))
      (node (ref "T2") (pin "3") (pinfunction "D_3") (pintype "passive"))
    )
    (net (code "97") (name "Net-(T3-D)") (class "Default")
      (node (ref "R60") (pin "2") (pinfunction "2_2") (pintype "passive"))
      (node (ref "T3") (pin "3") (pinfunction "D_3") (pintype "passive"))
    )
    (net (code "98") (name "Net-(T4-D)") (class "Default")
      (node (ref "R61") (pin "2") (pinfunction "2_2") (pintype "passive"))
      (node (ref "T4") (pin "3") (pinfunction "D_3") (pintype "passive"))
    )
    (net (code "99") (name "Net-(T5-D)") (class "Default")
      (node (ref "R62") (pin "2") (pinfunction "2_2") (pintype "passive"))
      (node (ref "T5") (pin "3") (pinfunction "D_3") (pintype "passive"))
    )
    (net (code "100") (name "Net-(T6-D)") (class "Default")
      (node (ref "R63") (pin "2") (pinfunction "2_2") (pintype "passive"))
      (node (ref "T6") (pin "3") (pinfunction "D_3") (pintype "passive"))
    )
    (net (code "101") (name "Net-(T7-D)") (class "Default")
      (node (ref "R64") (pin "2") (pinfunction "2_2") (pintype "passive"))
      (node (ref "T7") (pin "3") (pinfunction "D_3") (pintype "passive"))
    )
    (net (code "102") (name "Net-(T8-D)") (class "Default")
      (node (ref "R65") (pin "2") (pinfunction "2_2") (pintype "passive"))
      (node (ref "T8") (pin "3") (pinfunction "D_3") (pintype "passive"))
    )
    (net (code "103") (name "P3V3") (class "Default")
      (node (ref "C57") (pin "2") (pinfunction "2_2") (pintype "passive"))
      (node (ref "C94") (pin "2") (pinfunction "2_2") (pintype "passive"))
      (node (ref "IC10") (pin "10") (pinfunction "~{SRCLR}_10") (pintype "input"))
      (node (ref "IC10") (pin "16") (pinfunction "VCC_16") (pintype "power_in"))
      (node (ref "IC11") (pin "10") (pinfunction "~{SRCLR}_10") (pintype "input"))
      (node (ref "IC11") (pin "16") (pinfunction "VCC_16") (pintype "power_in"))
      (node (ref "LD1") (pin "2") (pinfunction "A_2") (pintype "passive"))
      (node (ref "LD1") (pin "4") (pinfunction "A_4") (pintype "passive"))
      (node (ref "LD2") (pin "2") (pinfunction "A_2") (pintype "passive"))
      (node (ref "LD2") (pin "4") (pinfunction "A_4") (pintype "passive"))
      (node (ref "LD3") (pin "2") (pinfunction "A_2") (pintype "passive"))
      (node (ref "LD3") (pin "4") (pinfunction "A_4") (pintype "passive"))
      (node (ref "LD4") (pin "2") (pinfunction "A_2") (pintype "passive"))
      (node (ref "LD4") (pin "4") (pinfunction "A_4") (pintype "passive"))
      (node (ref "LD5") (pin "2") (pinfunction "A_2") (pintype "passive"))
      (node (ref "R12") (pin "1") (pinfunction "1_1") (pintype "passive"))
      (node (ref "R13") (pin "1") (pinfunction "1_1") (pintype "passive"))
      (node (ref "R49") (pin "1") (pinfunction "1_1") (pintype "passive"))
      (node (ref "R5") (pin "1") (pinfunction "1_1") (pintype "passive"))
      (node (ref "R68") (pin "1") (pinfunction "1_1") (pintype "passive"))
      (node (ref "R69") (pin "1") (pinfunction "1_1") (pintype "passive"))
      (node (ref "R70") (pin "1") (pinfunction "1_1") (pintype "passive"))
      (node (ref "R71") (pin "1") (pinfunction "1_1") (pintype "passive"))
    )
    (net (code "104") (name "P3V3_MP1") (class "Default")
      (node (ref "LD5") (pin "4") (pinfunction "A_4") (pintype "passive"))
    )
    (net (code "105") (name "P12V0") (class "Default")
      (node (ref "R74") (pin "2") (pinfunction "2_2") (pintype "passive"))
    )
    (net (code "106") (name "P13V0") (class "Default")
      (node (ref "R3") (pin "2") (pinfunction "2_2") (pintype "passive"))
    )
  )
)
